# Transistores-v1.net
KiCad netlist of a schematic drawn in EAGLE
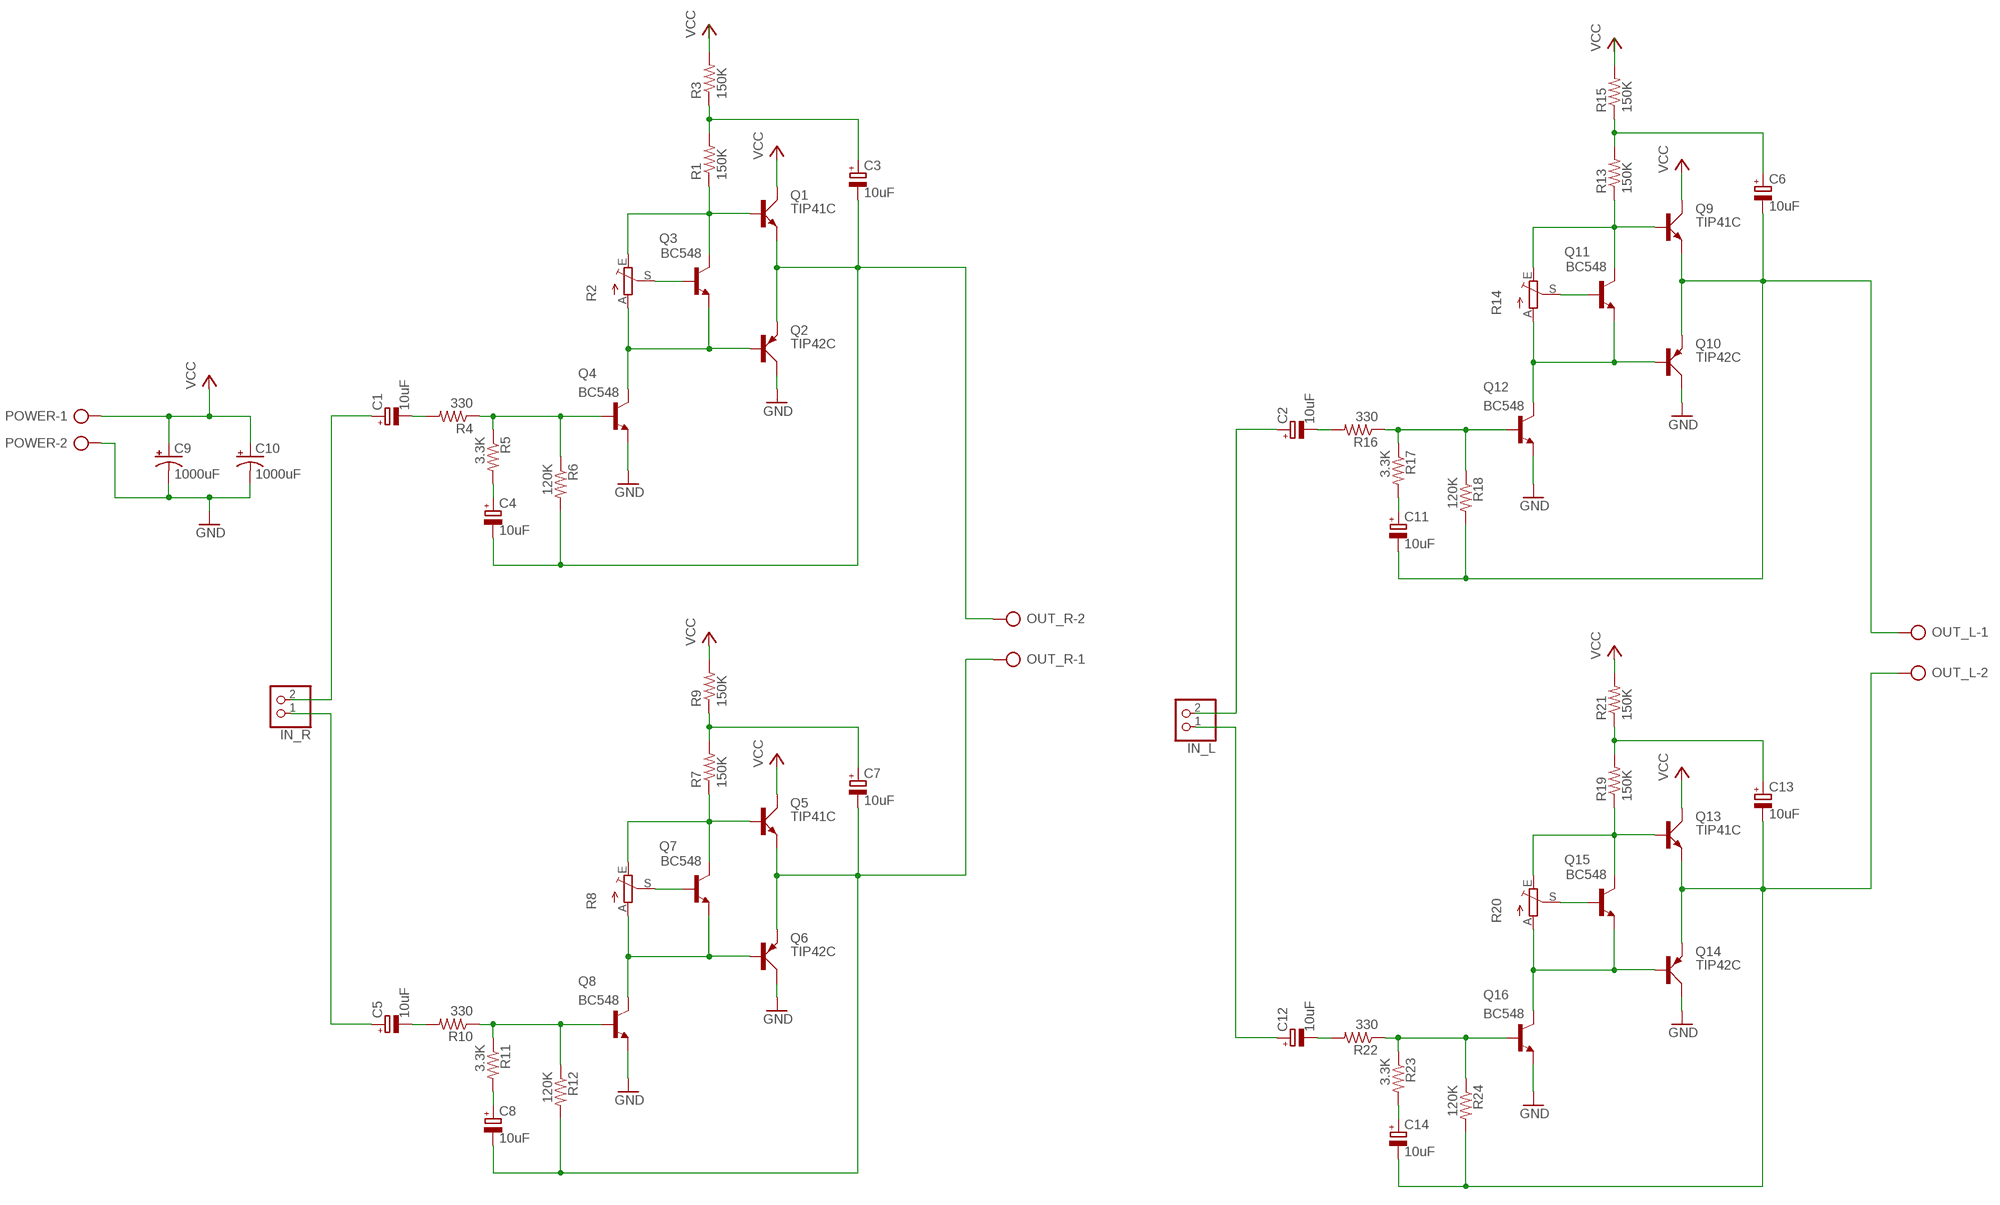
[diagram p0: schematic, sheet 1]

(export (version "E")
  (design (tool "Eeschema 10.0.6"))
  (components
    (comp (ref "C1")
      (value "10uF")
      (footprint "eagle-import:E2,5-5")
      (libsource (lib "eagle-import") (part "CPOL-EUE2.5-5"))
    )
    (comp (ref "C2")
      (value "10uF")
      (footprint "eagle-import:E2,5-5")
      (libsource (lib "eagle-import") (part "CPOL-EUE2.5-5"))
    )
    (comp (ref "C3")
      (value "10uF")
      (footprint "eagle-import:E2,5-5")
      (libsource (lib "eagle-import") (part "CPOL-EUE2.5-5"))
    )
    (comp (ref "C4")
      (value "10uF")
      (footprint "eagle-import:E2,5-5")
      (libsource (lib "eagle-import") (part "CPOL-EUE2.5-5"))
    )
    (comp (ref "C5")
      (value "10uF")
      (footprint "eagle-import:E2,5-5")
      (libsource (lib "eagle-import") (part "CPOL-EUE2.5-5"))
    )
    (comp (ref "C6")
      (value "10uF")
      (footprint "eagle-import:E2,5-5")
      (libsource (lib "eagle-import") (part "CPOL-EUE2.5-5"))
    )
    (comp (ref "C7")
      (value "10uF")
      (footprint "eagle-import:E2,5-5")
      (libsource (lib "eagle-import") (part "CPOL-EUE2.5-5"))
    )
    (comp (ref "C8")
      (value "10uF")
      (footprint "eagle-import:E2,5-5")
      (libsource (lib "eagle-import") (part "CPOL-EUE2.5-5"))
    )
    (comp (ref "C9")
      (value "1000uF")
      (footprint "eagle-import:E2,5-7")
      (libsource (lib "eagle-import") (part "CPOL-USE2.5-7"))
    )
    (comp (ref "C10")
      (value "1000uF")
      (footprint "eagle-import:E2,5-7")
      (libsource (lib "eagle-import") (part "CPOL-USE2.5-7"))
    )
    (comp (ref "C11")
      (value "10uF")
      (footprint "eagle-import:E2,5-5")
      (libsource (lib "eagle-import") (part "CPOL-EUE2.5-5"))
    )
    (comp (ref "C12")
      (value "10uF")
      (footprint "eagle-import:E2,5-5")
      (libsource (lib "eagle-import") (part "CPOL-EUE2.5-5"))
    )
    (comp (ref "C13")
      (value "10uF")
      (footprint "eagle-import:E2,5-5")
      (libsource (lib "eagle-import") (part "CPOL-EUE2.5-5"))
    )
    (comp (ref "C14")
      (value "10uF")
      (footprint "eagle-import:E2,5-5")
      (libsource (lib "eagle-import") (part "CPOL-EUE2.5-5"))
    )
    (comp (ref "IN_L")
      (value "PINHD-1X2")
      (footprint "eagle-import:1X02")
      (libsource (lib "eagle-import") (part "PINHD-1X2"))
    )
    (comp (ref "IN_R")
      (value "PINHD-1X2")
      (footprint "eagle-import:1X02")
      (libsource (lib "eagle-import") (part "PINHD-1X2"))
    )
    (comp (ref "OUT_L")
      (value "AK300/2")
      (footprint "eagle-import:AK300_2")
      (libsource (lib "eagle-import") (part "AK300/2"))
    )
    (comp (ref "OUT_R")
      (value "AK300/2")
      (footprint "eagle-import:AK300_2")
      (libsource (lib "eagle-import") (part "AK300/2"))
    )
    (comp (ref "POWER")
      (value "AK300/2")
      (footprint "eagle-import:AK300_2")
      (libsource (lib "eagle-import") (part "AK300/2"))
    )
    (comp (ref "Q1")
      (value "TIP41C")
      (footprint "eagle-import:TO220AV")
      (libsource (lib "eagle-import") (part "TIP41C"))
    )
    (comp (ref "Q2")
      (value "TIP42C")
      (footprint "eagle-import:TO220AV")
      (libsource (lib "eagle-import") (part "TIP42C"))
    )
    (comp (ref "Q3")
      (value "BC548")
      (footprint "eagle-import:TO92-EBC")
      (libsource (lib "eagle-import") (part "BC548"))
    )
    (comp (ref "Q4")
      (value "BC548")
      (footprint "eagle-import:TO92-EBC")
      (libsource (lib "eagle-import") (part "BC548"))
    )
    (comp (ref "Q5")
      (value "TIP41C")
      (footprint "eagle-import:TO220AV")
      (libsource (lib "eagle-import") (part "TIP41C"))
    )
    (comp (ref "Q6")
      (value "TIP42C")
      (footprint "eagle-import:TO220AV")
      (libsource (lib "eagle-import") (part "TIP42C"))
    )
    (comp (ref "Q7")
      (value "BC548")
      (footprint "eagle-import:TO92-EBC")
      (libsource (lib "eagle-import") (part "BC548"))
    )
    (comp (ref "Q8")
      (value "BC548")
      (footprint "eagle-import:TO92-EBC")
      (libsource (lib "eagle-import") (part "BC548"))
    )
    (comp (ref "Q9")
      (value "TIP41C")
      (footprint "eagle-import:TO220AV")
      (libsource (lib "eagle-import") (part "TIP41C"))
    )
    (comp (ref "Q10")
      (value "TIP42C")
      (footprint "eagle-import:TO220AV")
      (libsource (lib "eagle-import") (part "TIP42C"))
    )
    (comp (ref "Q11")
      (value "BC548")
      (footprint "eagle-import:TO92-EBC")
      (libsource (lib "eagle-import") (part "BC548"))
    )
    (comp (ref "Q12")
      (value "BC548")
      (footprint "eagle-import:TO92-EBC")
      (libsource (lib "eagle-import") (part "BC548"))
    )
    (comp (ref "Q13")
      (value "TIP41C")
      (footprint "eagle-import:TO220AV")
      (libsource (lib "eagle-import") (part "TIP41C"))
    )
    (comp (ref "Q14")
      (value "TIP42C")
      (footprint "eagle-import:TO220AV")
      (libsource (lib "eagle-import") (part "TIP42C"))
    )
    (comp (ref "Q15")
      (value "BC548")
      (footprint "eagle-import:TO92-EBC")
      (libsource (lib "eagle-import") (part "BC548"))
    )
    (comp (ref "Q16")
      (value "BC548")
      (footprint "eagle-import:TO92-EBC")
      (libsource (lib "eagle-import") (part "BC548"))
    )
    (comp (ref "R1")
      (value "150K")
      (footprint "eagle-import:0204_7")
      (libsource (lib "eagle-import") (part "R-US_0204/7"))
    )
    (comp (ref "R2")
      (value "TRIM_EU-LI10")
      (footprint "eagle-import:LI10")
      (libsource (lib "eagle-import") (part "TRIM_EU-LI10"))
    )
    (comp (ref "R3")
      (value "150K")
      (footprint "eagle-import:0204_7")
      (libsource (lib "eagle-import") (part "R-US_0204/7"))
    )
    (comp (ref "R4")
      (value "330")
      (footprint "eagle-import:0204_7")
      (libsource (lib "eagle-import") (part "R-US_0204/7"))
    )
    (comp (ref "R5")
      (value "3.3K")
      (footprint "eagle-import:0204_7")
      (libsource (lib "eagle-import") (part "R-US_0204/7"))
    )
    (comp (ref "R6")
      (value "120K")
      (footprint "eagle-import:0204_7")
      (libsource (lib "eagle-import") (part "R-US_0204/7"))
    )
    (comp (ref "R7")
      (value "150K")
      (footprint "eagle-import:0204_7")
      (libsource (lib "eagle-import") (part "R-US_0204/7"))
    )
    (comp (ref "R8")
      (value "TRIM_EU-LI10")
      (footprint "eagle-import:LI10")
      (libsource (lib "eagle-import") (part "TRIM_EU-LI10"))
    )
    (comp (ref "R9")
      (value "150K")
      (footprint "eagle-import:0204_7")
      (libsource (lib "eagle-import") (part "R-US_0204/7"))
    )
    (comp (ref "R10")
      (value "330")
      (footprint "eagle-import:0204_7")
      (libsource (lib "eagle-import") (part "R-US_0204/7"))
    )
    (comp (ref "R11")
      (value "3.3K")
      (footprint "eagle-import:0204_7")
      (libsource (lib "eagle-import") (part "R-US_0204/7"))
    )
    (comp (ref "R12")
      (value "120K")
      (footprint "eagle-import:0204_7")
      (libsource (lib "eagle-import") (part "R-US_0204/7"))
    )
    (comp (ref "R13")
      (value "150K")
      (footprint "eagle-import:0204_7")
      (libsource (lib "eagle-import") (part "R-US_0204/7"))
    )
    (comp (ref "R14")
      (value "TRIM_EU-LI10")
      (footprint "eagle-import:LI10")
      (libsource (lib "eagle-import") (part "TRIM_EU-LI10"))
    )
    (comp (ref "R15")
      (value "150K")
      (footprint "eagle-import:0204_7")
      (libsource (lib "eagle-import") (part "R-US_0204/7"))
    )
    (comp (ref "R16")
      (value "330")
      (footprint "eagle-import:0204_7")
      (libsource (lib "eagle-import") (part "R-US_0204/7"))
    )
    (comp (ref "R17")
      (value "3.3K")
      (footprint "eagle-import:0204_7")
      (libsource (lib "eagle-import") (part "R-US_0204/7"))
    )
    (comp (ref "R18")
      (value "120K")
      (footprint "eagle-import:0204_7")
      (libsource (lib "eagle-import") (part "R-US_0204/7"))
    )
    (comp (ref "R19")
      (value "150K")
      (footprint "eagle-import:0204_7")
      (libsource (lib "eagle-import") (part "R-US_0204/7"))
    )
    (comp (ref "R20")
      (value "TRIM_EU-LI10")
      (footprint "eagle-import:LI10")
      (libsource (lib "eagle-import") (part "TRIM_EU-LI10"))
    )
    (comp (ref "R21")
      (value "150K")
      (footprint "eagle-import:0204_7")
      (libsource (lib "eagle-import") (part "R-US_0204/7"))
    )
    (comp (ref "R22")
      (value "330")
      (footprint "eagle-import:0204_7")
      (libsource (lib "eagle-import") (part "R-US_0204/7"))
    )
    (comp (ref "R23")
      (value "3.3K")
      (footprint "eagle-import:0204_7")
      (libsource (lib "eagle-import") (part "R-US_0204/7"))
    )
    (comp (ref "R24")
      (value "120K")
      (footprint "eagle-import:0204_7")
      (libsource (lib "eagle-import") (part "R-US_0204/7"))
    )
  )
  (nets
    (net (code "1") (name "GND") (class "Default")
      (node (ref "C10") (pin "-") (pinfunction "-_-") (pintype "passive"))
      (node (ref "C9") (pin "-") (pinfunction "-_-") (pintype "passive"))
      (node (ref "POWER") (pin "2") (pinfunction "KL_2") (pintype "passive"))
      (node (ref "Q10") (pin "C") (pinfunction "C_C") (pintype "passive"))
      (node (ref "Q12") (pin "E") (pinfunction "E_E") (pintype "passive"))
      (node (ref "Q14") (pin "C") (pinfunction "C_C") (pintype "passive"))
      (node (ref "Q16") (pin "E") (pinfunction "E_E") (pintype "passive"))
      (node (ref "Q2") (pin "C") (pinfunction "C_C") (pintype "passive"))
      (node (ref "Q4") (pin "E") (pinfunction "E_E") (pintype "passive"))
      (node (ref "Q6") (pin "C") (pinfunction "C_C") (pintype "passive"))
      (node (ref "Q8") (pin "E") (pinfunction "E_E") (pintype "passive"))
    )
    (net (code "2") (name "Net-(C1-Pad+)") (class "Default")
      (node (ref "C1") (pin "+") (pinfunction "+_+") (pintype "passive"))
      (node (ref "IN_R") (pin "2") (pinfunction "2_2") (pintype "passive"))
    )
    (net (code "3") (name "Net-(C1-Pad-)") (class "Default")
      (node (ref "C1") (pin "-") (pinfunction "-_-") (pintype "passive"))
      (node (ref "R4") (pin "2") (pinfunction "2_2") (pintype "passive"))
    )
    (net (code "4") (name "Net-(C2-Pad+)") (class "Default")
      (node (ref "C2") (pin "+") (pinfunction "+_+") (pintype "passive"))
      (node (ref "IN_L") (pin "2") (pinfunction "2_2") (pintype "passive"))
    )
    (net (code "5") (name "Net-(C2-Pad-)") (class "Default")
      (node (ref "C2") (pin "-") (pinfunction "-_-") (pintype "passive"))
      (node (ref "R16") (pin "2") (pinfunction "2_2") (pintype "passive"))
    )
    (net (code "6") (name "Net-(C3-Pad+)") (class "Default")
      (node (ref "C3") (pin "+") (pinfunction "+_+") (pintype "passive"))
      (node (ref "R1") (pin "2") (pinfunction "2_2") (pintype "passive"))
      (node (ref "R3") (pin "1") (pinfunction "1_1") (pintype "passive"))
    )
    (net (code "7") (name "Net-(C4-Pad+)") (class "Default")
      (node (ref "C4") (pin "+") (pinfunction "+_+") (pintype "passive"))
      (node (ref "R5") (pin "2") (pinfunction "2_2") (pintype "passive"))
    )
    (net (code "8") (name "Net-(C5-Pad+)") (class "Default")
      (node (ref "C5") (pin "+") (pinfunction "+_+") (pintype "passive"))
      (node (ref "IN_R") (pin "1") (pinfunction "1_1") (pintype "passive"))
    )
    (net (code "9") (name "Net-(C5-Pad-)") (class "Default")
      (node (ref "C5") (pin "-") (pinfunction "-_-") (pintype "passive"))
      (node (ref "R10") (pin "2") (pinfunction "2_2") (pintype "passive"))
    )
    (net (code "10") (name "Net-(C6-Pad+)") (class "Default")
      (node (ref "C6") (pin "+") (pinfunction "+_+") (pintype "passive"))
      (node (ref "R13") (pin "2") (pinfunction "2_2") (pintype "passive"))
      (node (ref "R15") (pin "1") (pinfunction "1_1") (pintype "passive"))
    )
    (net (code "11") (name "Net-(C7-Pad+)") (class "Default")
      (node (ref "C7") (pin "+") (pinfunction "+_+") (pintype "passive"))
      (node (ref "R7") (pin "2") (pinfunction "2_2") (pintype "passive"))
      (node (ref "R9") (pin "1") (pinfunction "1_1") (pintype "passive"))
    )
    (net (code "12") (name "Net-(C8-Pad+)") (class "Default")
      (node (ref "C8") (pin "+") (pinfunction "+_+") (pintype "passive"))
      (node (ref "R11") (pin "2") (pinfunction "2_2") (pintype "passive"))
    )
    (net (code "13") (name "Net-(C11-Pad+)") (class "Default")
      (node (ref "C11") (pin "+") (pinfunction "+_+") (pintype "passive"))
      (node (ref "R17") (pin "2") (pinfunction "2_2") (pintype "passive"))
    )
    (net (code "14") (name "Net-(C12-Pad+)") (class "Default")
      (node (ref "C12") (pin "+") (pinfunction "+_+") (pintype "passive"))
      (node (ref "IN_L") (pin "1") (pinfunction "1_1") (pintype "passive"))
    )
    (net (code "15") (name "Net-(C12-Pad-)") (class "Default")
      (node (ref "C12") (pin "-") (pinfunction "-_-") (pintype "passive"))
      (node (ref "R22") (pin "2") (pinfunction "2_2") (pintype "passive"))
    )
    (net (code "16") (name "Net-(C13-Pad+)") (class "Default")
      (node (ref "C13") (pin "+") (pinfunction "+_+") (pintype "passive"))
      (node (ref "R19") (pin "2") (pinfunction "2_2") (pintype "passive"))
      (node (ref "R21") (pin "1") (pinfunction "1_1") (pintype "passive"))
    )
    (net (code "17") (name "Net-(C14-Pad+)") (class "Default")
      (node (ref "C14") (pin "+") (pinfunction "+_+") (pintype "passive"))
      (node (ref "R23") (pin "2") (pinfunction "2_2") (pintype "passive"))
    )
    (net (code "18") (name "Net-(OUT_LA-KL)") (class "Default")
      (node (ref "C11") (pin "-") (pinfunction "-_-") (pintype "passive"))
      (node (ref "C6") (pin "-") (pinfunction "-_-") (pintype "passive"))
      (node (ref "OUT_L") (pin "1") (pinfunction "KL_1") (pintype "passive"))
      (node (ref "Q10") (pin "E") (pinfunction "E_E") (pintype "passive"))
      (node (ref "Q9") (pin "E") (pinfunction "E_E") (pintype "passive"))
      (node (ref "R18") (pin "2") (pinfunction "2_2") (pintype "passive"))
    )
    (net (code "19") (name "Net-(OUT_LB-KL)") (class "Default")
      (node (ref "C13") (pin "-") (pinfunction "-_-") (pintype "passive"))
      (node (ref "C14") (pin "-") (pinfunction "-_-") (pintype "passive"))
      (node (ref "OUT_L") (pin "2") (pinfunction "KL_2") (pintype "passive"))
      (node (ref "Q13") (pin "E") (pinfunction "E_E") (pintype "passive"))
      (node (ref "Q14") (pin "E") (pinfunction "E_E") (pintype "passive"))
      (node (ref "R24") (pin "2") (pinfunction "2_2") (pintype "passive"))
    )
    (net (code "20") (name "Net-(OUT_RA-KL)") (class "Default")
      (node (ref "C7") (pin "-") (pinfunction "-_-") (pintype "passive"))
      (node (ref "C8") (pin "-") (pinfunction "-_-") (pintype "passive"))
      (node (ref "OUT_R") (pin "1") (pinfunction "KL_1") (pintype "passive"))
      (node (ref "Q5") (pin "E") (pinfunction "E_E") (pintype "passive"))
      (node (ref "Q6") (pin "E") (pinfunction "E_E") (pintype "passive"))
      (node (ref "R12") (pin "2") (pinfunction "2_2") (pintype "passive"))
    )
    (net (code "21") (name "Net-(OUT_RB-KL)") (class "Default")
      (node (ref "C3") (pin "-") (pinfunction "-_-") (pintype "passive"))
      (node (ref "C4") (pin "-") (pinfunction "-_-") (pintype "passive"))
      (node (ref "OUT_R") (pin "2") (pinfunction "KL_2") (pintype "passive"))
      (node (ref "Q1") (pin "E") (pinfunction "E_E") (pintype "passive"))
      (node (ref "Q2") (pin "E") (pinfunction "E_E") (pintype "passive"))
      (node (ref "R6") (pin "2") (pinfunction "2_2") (pintype "passive"))
    )
    (net (code "22") (name "Net-(Q1-PadB)") (class "Default")
      (node (ref "Q1") (pin "B") (pinfunction "B_B") (pintype "passive"))
      (node (ref "Q3") (pin "C") (pinfunction "C_C") (pintype "passive"))
      (node (ref "R1") (pin "1") (pinfunction "1_1") (pintype "passive"))
      (node (ref "R2") (pin "E") (pinfunction "E_E") (pintype "passive"))
    )
    (net (code "23") (name "Net-(Q2-PadB)") (class "Default")
      (node (ref "Q2") (pin "B") (pinfunction "B_B") (pintype "passive"))
      (node (ref "Q3") (pin "E") (pinfunction "E_E") (pintype "passive"))
      (node (ref "Q4") (pin "C") (pinfunction "C_C") (pintype "passive"))
      (node (ref "R2") (pin "A") (pinfunction "A_A") (pintype "passive"))
    )
    (net (code "24") (name "Net-(Q3-PadB)") (class "Default")
      (node (ref "Q3") (pin "B") (pinfunction "B_B") (pintype "passive"))
      (node (ref "R2") (pin "S") (pinfunction "S_S") (pintype "passive"))
    )
    (net (code "25") (name "Net-(Q4-PadB)") (class "Default")
      (node (ref "Q4") (pin "B") (pinfunction "B_B") (pintype "passive"))
      (node (ref "R4") (pin "1") (pinfunction "1_1") (pintype "passive"))
      (node (ref "R5") (pin "1") (pinfunction "1_1") (pintype "passive"))
      (node (ref "R6") (pin "1") (pinfunction "1_1") (pintype "passive"))
    )
    (net (code "26") (name "Net-(Q5-PadB)") (class "Default")
      (node (ref "Q5") (pin "B") (pinfunction "B_B") (pintype "passive"))
      (node (ref "Q7") (pin "C") (pinfunction "C_C") (pintype "passive"))
      (node (ref "R7") (pin "1") (pinfunction "1_1") (pintype "passive"))
      (node (ref "R8") (pin "E") (pinfunction "E_E") (pintype "passive"))
    )
    (net (code "27") (name "Net-(Q6-PadB)") (class "Default")
      (node (ref "Q6") (pin "B") (pinfunction "B_B") (pintype "passive"))
      (node (ref "Q7") (pin "E") (pinfunction "E_E") (pintype "passive"))
      (node (ref "Q8") (pin "C") (pinfunction "C_C") (pintype "passive"))
      (node (ref "R8") (pin "A") (pinfunction "A_A") (pintype "passive"))
    )
    (net (code "28") (name "Net-(Q7-PadB)") (class "Default")
      (node (ref "Q7") (pin "B") (pinfunction "B_B") (pintype "passive"))
      (node (ref "R8") (pin "S") (pinfunction "S_S") (pintype "passive"))
    )
    (net (code "29") (name "Net-(Q8-PadB)") (class "Default")
      (node (ref "Q8") (pin "B") (pinfunction "B_B") (pintype "passive"))
      (node (ref "R10") (pin "1") (pinfunction "1_1") (pintype "passive"))
      (node (ref "R11") (pin "1") (pinfunction "1_1") (pintype "passive"))
      (node (ref "R12") (pin "1") (pinfunction "1_1") (pintype "passive"))
    )
    (net (code "30") (name "Net-(Q10-PadB)") (class "Default")
      (node (ref "Q10") (pin "B") (pinfunction "B_B") (pintype "passive"))
      (node (ref "Q11") (pin "E") (pinfunction "E_E") (pintype "passive"))
      (node (ref "Q12") (pin "C") (pinfunction "C_C") (pintype "passive"))
      (node (ref "R14") (pin "A") (pinfunction "A_A") (pintype "passive"))
    )
    (net (code "31") (name "Net-(Q11-PadB)") (class "Default")
      (node (ref "Q11") (pin "B") (pinfunction "B_B") (pintype "passive"))
      (node (ref "R14") (pin "S") (pinfunction "S_S") (pintype "passive"))
    )
    (net (code "32") (name "Net-(Q11-PadC)") (class "Default")
      (node (ref "Q11") (pin "C") (pinfunction "C_C") (pintype "passive"))
      (node (ref "Q9") (pin "B") (pinfunction "B_B") (pintype "passive"))
      (node (ref "R13") (pin "1") (pinfunction "1_1") (pintype "passive"))
      (node (ref "R14") (pin "E") (pinfunction "E_E") (pintype "passive"))
    )
    (net (code "33") (name "Net-(Q12-PadB)") (class "Default")
      (node (ref "Q12") (pin "B") (pinfunction "B_B") (pintype "passive"))
      (node (ref "R16") (pin "1") (pinfunction "1_1") (pintype "passive"))
      (node (ref "R17") (pin "1") (pinfunction "1_1") (pintype "passive"))
      (node (ref "R18") (pin "1") (pinfunction "1_1") (pintype "passive"))
    )
    (net (code "34") (name "Net-(Q13-PadB)") (class "Default")
      (node (ref "Q13") (pin "B") (pinfunction "B_B") (pintype "passive"))
      (node (ref "Q15") (pin "C") (pinfunction "C_C") (pintype "passive"))
      (node (ref "R19") (pin "1") (pinfunction "1_1") (pintype "passive"))
      (node (ref "R20") (pin "E") (pinfunction "E_E") (pintype "passive"))
    )
    (net (code "35") (name "Net-(Q14-PadB)") (class "Default")
      (node (ref "Q14") (pin "B") (pinfunction "B_B") (pintype "passive"))
      (node (ref "Q15") (pin "E") (pinfunction "E_E") (pintype "passive"))
      (node (ref "Q16") (pin "C") (pinfunction "C_C") (pintype "passive"))
      (node (ref "R20") (pin "A") (pinfunction "A_A") (pintype "passive"))
    )
    (net (code "36") (name "Net-(Q15-PadB)") (class "Default")
      (node (ref "Q15") (pin "B") (pinfunction "B_B") (pintype "passive"))
      (node (ref "R20") (pin "S") (pinfunction "S_S") (pintype "passive"))
    )
    (net (code "37") (name "Net-(Q16-PadB)") (class "Default")
      (node (ref "Q16") (pin "B") (pinfunction "B_B") (pintype "passive"))
      (node (ref "R22") (pin "1") (pinfunction "1_1") (pintype "passive"))
      (node (ref "R23") (pin "1") (pinfunction "1_1") (pintype "passive"))
      (node (ref "R24") (pin "1") (pinfunction "1_1") (pintype "passive"))
    )
    (net (code "38") (name "VCC") (class "Default")
      (node (ref "C10") (pin "+") (pinfunction "+_+") (pintype "passive"))
      (node (ref "C9") (pin "+") (pinfunction "+_+") (pintype "passive"))
      (node (ref "POWER") (pin "1") (pinfunction "KL_1") (pintype "passive"))
      (node (ref "Q1") (pin "C") (pinfunction "C_C") (pintype "passive"))
      (node (ref "Q13") (pin "C") (pinfunction "C_C") (pintype "passive"))
      (node (ref "Q5") (pin "C") (pinfunction "C_C") (pintype "passive"))
      (node (ref "Q9") (pin "C") (pinfunction "C_C") (pintype "passive"))
      (node (ref "R15") (pin "2") (pinfunction "2_2") (pintype "passive"))
      (node (ref "R21") (pin "2") (pinfunction "2_2") (pintype "passive"))
      (node (ref "R3") (pin "2") (pinfunction "2_2") (pintype "passive"))
      (node (ref "R9") (pin "2") (pinfunction "2_2") (pintype "passive"))
    )
  )
)
